# sch_light_rgb.net
KiCad netlist of a schematic drawn in EasyEDA
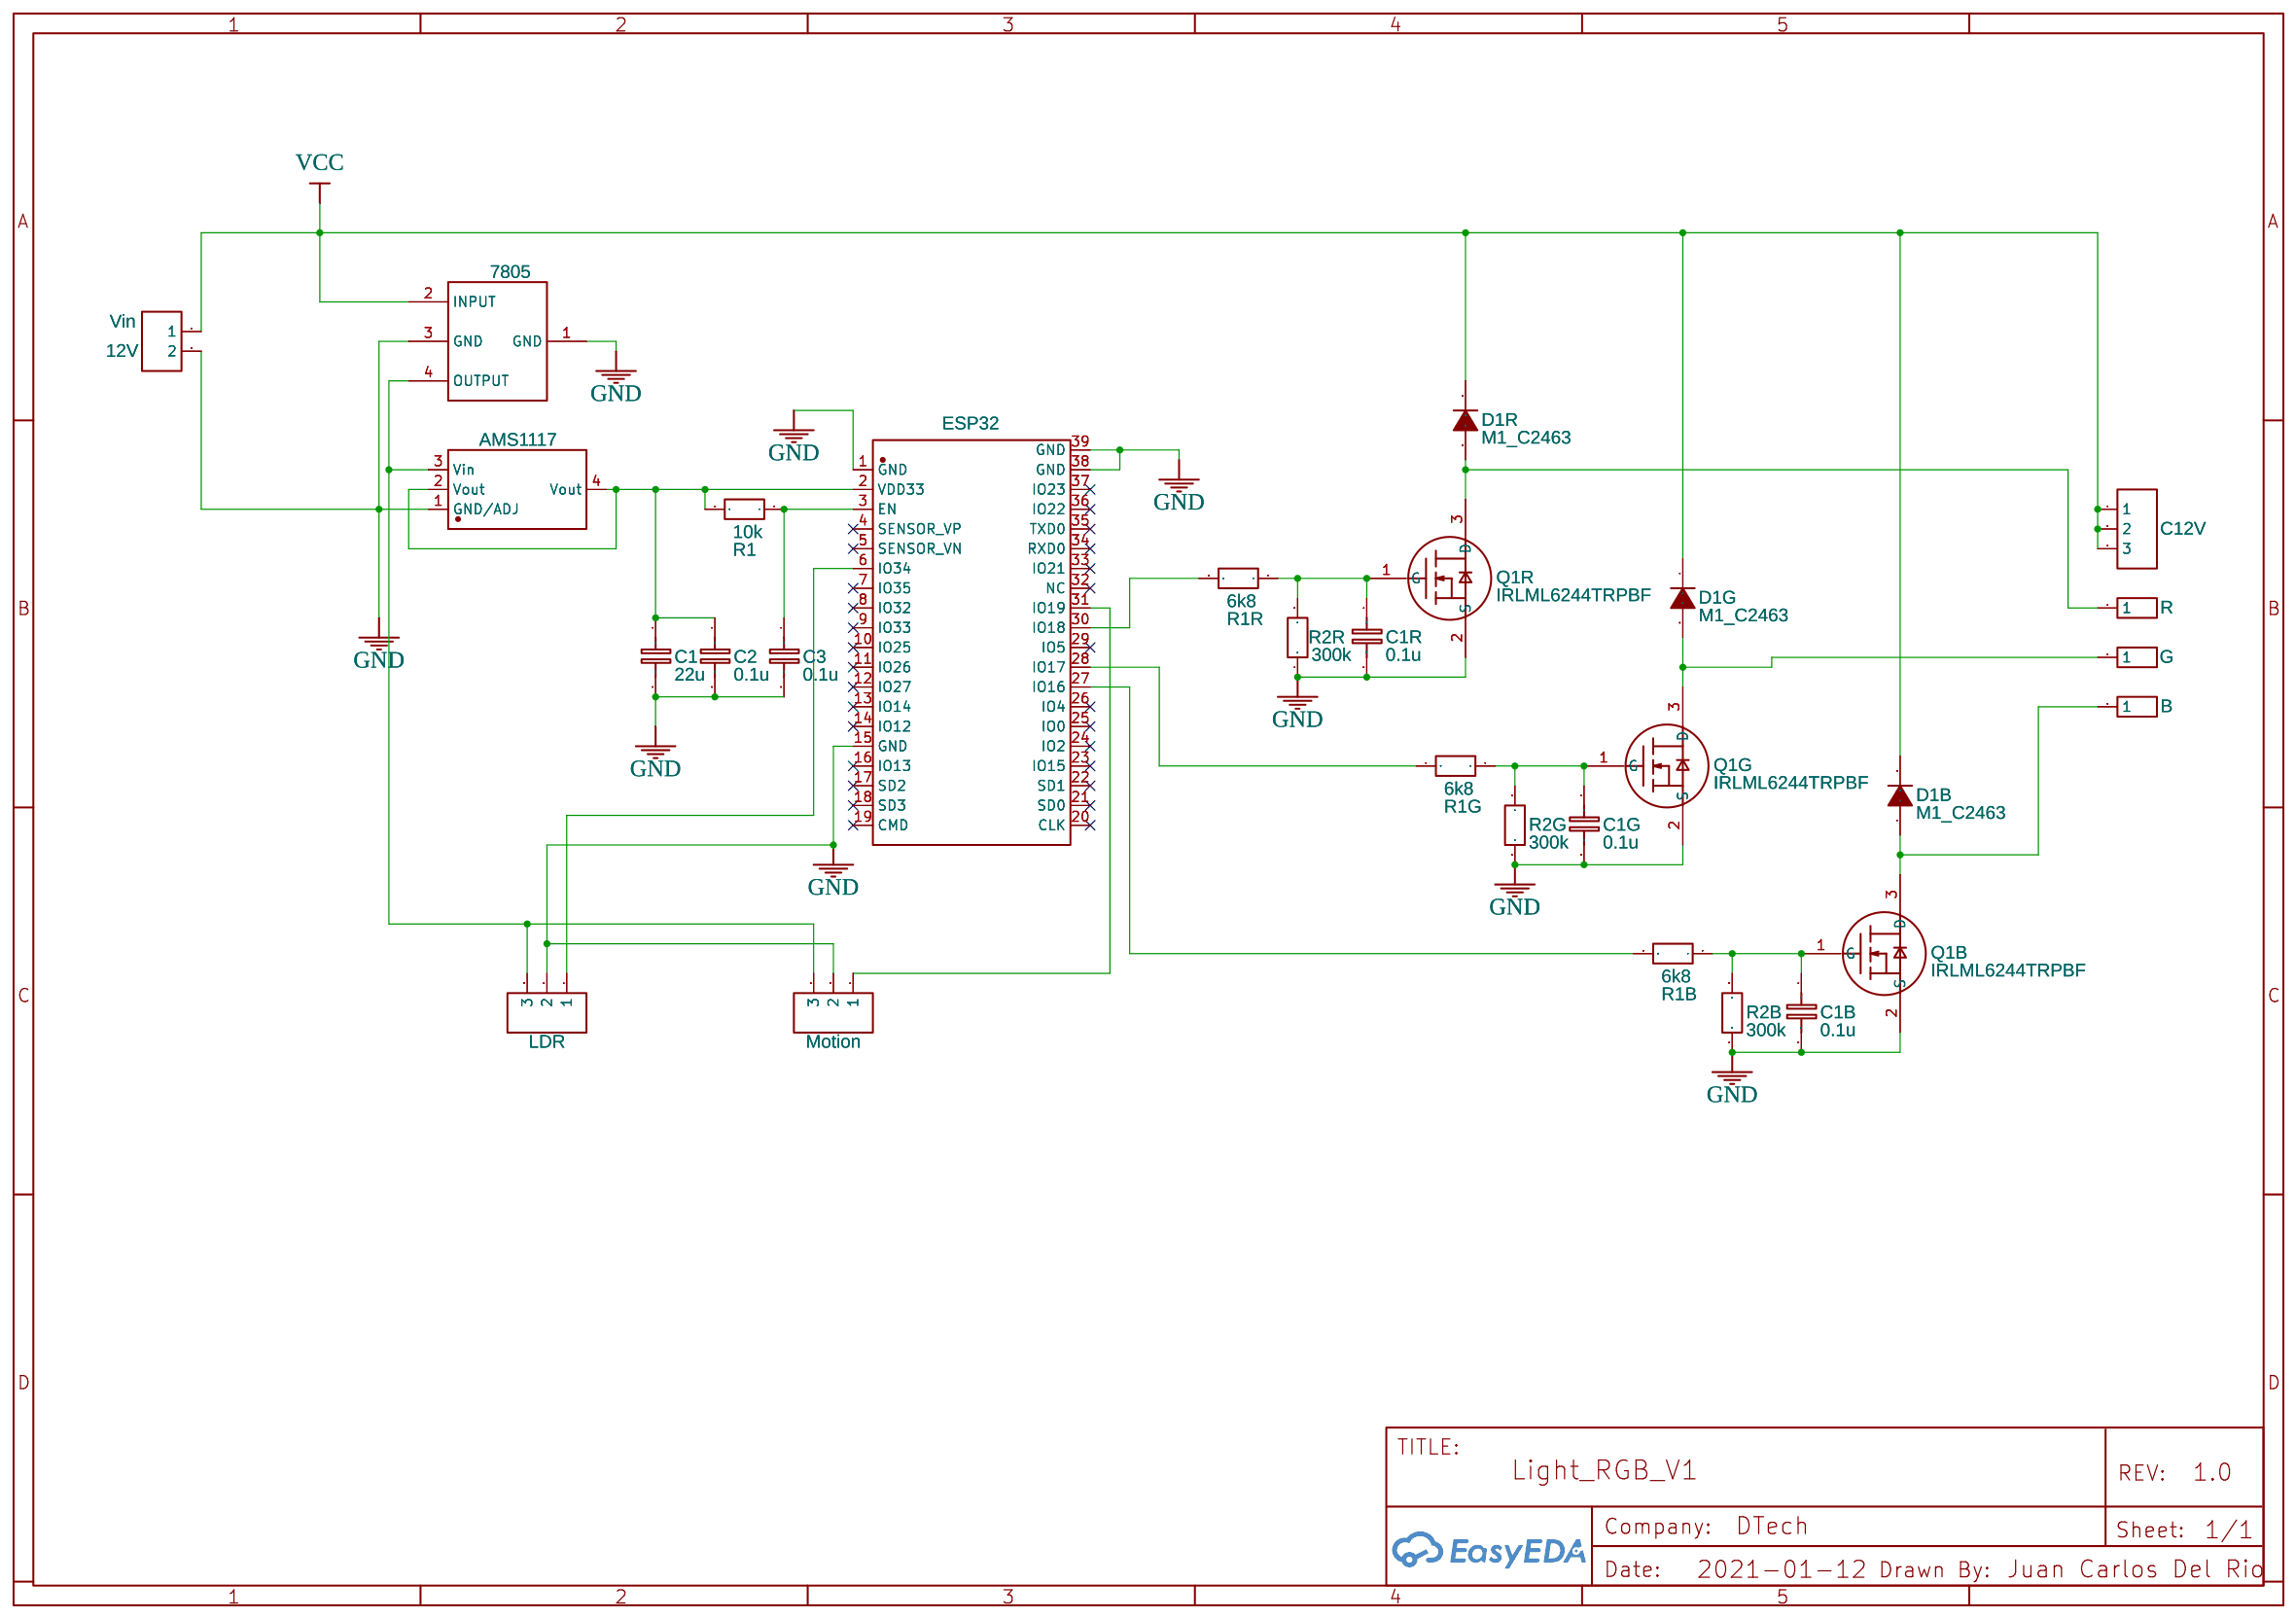
[diagram p0: schematic sheet]

(export (version "E")
  (design (tool "Eeschema 10.0.6"))
  (components
    (comp (ref "12V") (value "Vin") (libsource (lib "") (part "HDR-F-2.54_1x2")))
    (comp (ref "7805") (value "LM7805 SOT223-4") (libsource (lib "") (part "LM7805 SOT223-4")))
    (comp (ref "AMS1117")
      (value "AMS1117-3.3")
      (fields (field (name "Manufacturer") "AMS"))
      (libsource (lib "") (part "AMS1117-3.3"))
    )
    (comp (ref "B") (value "B") (libsource (lib "") (part "HDR-M-2.54_1x1_2")))
    (comp (ref "C1") (value "22u") (libsource (lib "") (part "C_0805_EU")))
    (comp (ref "C1B") (value "0.1u") (libsource (lib "") (part "C_0805_EU_1")))
    (comp (ref "C1G") (value "0.1u") (libsource (lib "") (part "C_0805_EU_2")))
    (comp (ref "C1R") (value "0.1u") (libsource (lib "") (part "C_0805_EU_3")))
    (comp (ref "C2") (value "0.1u") (libsource (lib "") (part "C_0805_EU")))
    (comp (ref "C3") (value "0.1u") (libsource (lib "") (part "C_0805_EU")))
    (comp (ref "C12V") (value "C12V") (libsource (lib "") (part "HDR-F-2.54_1x3")))
    (comp (ref "D1B")
      (value "M1_C2463")
      (fields (field (name "Manufacturer Part") "M1") (field (name "Manufacturer") "MDD"))
      (libsource (lib "") (part "M1_C2463_1"))
    )
    (comp (ref "D1G")
      (value "M1_C2463")
      (fields (field (name "Manufacturer Part") "M1") (field (name "Manufacturer") "MDD"))
      (libsource (lib "") (part "M1_C2463_2"))
    )
    (comp (ref "D1R")
      (value "M1_C2463")
      (fields (field (name "Manufacturer Part") "M1") (field (name "Manufacturer") "MDD"))
      (libsource (lib "") (part "M1_C2463"))
    )
    (comp (ref "ESP32")
      (value "ESP32-WROOM-32")
      (fields (field (name "Manufacturer") "Espressif Systems"))
      (libsource (lib "") (part "ESP32-WROOM-32"))
    )
    (comp (ref "G") (value "G") (libsource (lib "") (part "HDR-M-2.54_1x1")))
    (comp (ref "LDR") (value "LDR") (libsource (lib "") (part "HDR-F-2.54_1x3_1")))
    (comp (ref "MOTION") (value "Motion") (libsource (lib "") (part "HDR-F-2.54_1x3_2")))
    (comp (ref "Q1B")
      (value "IRLML6244TRPBF")
      (fields (field (name "Manufacturer") "Infineon"))
      (libsource (lib "") (part "IRLML6244TRPBF_2"))
    )
    (comp (ref "Q1G")
      (value "IRLML6244TRPBF")
      (fields (field (name "Manufacturer") "Infineon"))
      (libsource (lib "") (part "IRLML6244TRPBF"))
    )
    (comp (ref "Q1R")
      (value "IRLML6244TRPBF")
      (fields (field (name "Manufacturer") "Infineon"))
      (libsource (lib "") (part "IRLML6244TRPBF_1"))
    )
    (comp (ref "R") (value "R") (libsource (lib "") (part "HDR-M-2.54_1x1_1")))
    (comp (ref "R1") (value "10k") (libsource (lib "") (part "R_1206_EU_2")))
    (comp (ref "R1B") (value "6k8") (libsource (lib "") (part "R_1206_EU_1")))
    (comp (ref "R1G") (value "6k8") (libsource (lib "") (part "R_1206_EU_3")))
    (comp (ref "R1R") (value "6k8") (libsource (lib "") (part "R_1206_EU")))
    (comp (ref "R2B") (value "300k") (libsource (lib "") (part "R_1206_EU_5")))
    (comp (ref "R2G") (value "300k") (libsource (lib "") (part "R_1206_EU_6")))
    (comp (ref "R2R") (value "300k") (libsource (lib "") (part "R_1206_EU_4")))
  )
  (nets
    (net (code "1") (name "GND") (class "Default")
      (node (ref "12V") (pin "2") (pinfunction "2_2") (pintype "input"))
      (node (ref "7805") (pin "1") (pinfunction "GND_1") (pintype "unspecified"))
      (node (ref "7805") (pin "3") (pinfunction "GND_3") (pintype "unspecified"))
      (node (ref "AMS1117") (pin "1") (pinfunction "GND/ADJ_1") (pintype "unspecified"))
      (node (ref "C1") (pin "2") (pinfunction "2_2") (pintype "unspecified"))
      (node (ref "C1B") (pin "2") (pinfunction "2_2") (pintype "unspecified"))
      (node (ref "C1G") (pin "2") (pinfunction "2_2") (pintype "unspecified"))
      (node (ref "C1R") (pin "2") (pinfunction "2_2") (pintype "unspecified"))
      (node (ref "C2") (pin "2") (pinfunction "2_2") (pintype "unspecified"))
      (node (ref "C3") (pin "2") (pinfunction "2_2") (pintype "unspecified"))
      (node (ref "ESP32") (pin "1") (pinfunction "GND_1") (pintype "unspecified"))
      (node (ref "ESP32") (pin "15") (pinfunction "GND_15") (pintype "unspecified"))
      (node (ref "ESP32") (pin "38") (pinfunction "GND_38") (pintype "unspecified"))
      (node (ref "ESP32") (pin "39") (pinfunction "GND_39") (pintype "unspecified"))
      (node (ref "LDR") (pin "2") (pinfunction "2_2") (pintype "input"))
      (node (ref "MOTION") (pin "2") (pinfunction "2_2") (pintype "input"))
      (node (ref "Q1B") (pin "2") (pinfunction "S_2") (pintype "unspecified"))
      (node (ref "Q1G") (pin "2") (pinfunction "S_2") (pintype "unspecified"))
      (node (ref "Q1R") (pin "2") (pinfunction "S_2") (pintype "unspecified"))
      (node (ref "R2B") (pin "1") (pinfunction "1_1") (pintype "unspecified"))
      (node (ref "R2G") (pin "1") (pinfunction "1_1") (pintype "unspecified"))
      (node (ref "R2R") (pin "1") (pinfunction "1_1") (pintype "unspecified"))
    )
    (net (code "2") (name "Net-(7805-OUTPUT)") (class "Default")
      (node (ref "7805") (pin "4") (pinfunction "OUTPUT_4") (pintype "unspecified"))
      (node (ref "AMS1117") (pin "3") (pinfunction "Vin_3") (pintype "unspecified"))
      (node (ref "LDR") (pin "3") (pinfunction "3_3") (pintype "input"))
      (node (ref "MOTION") (pin "3") (pinfunction "3_3") (pintype "input"))
    )
    (net (code "3") (name "Net-(D1B-A)") (class "Default")
      (node (ref "B") (pin "1") (pinfunction "1_1") (pintype "input"))
      (node (ref "D1B") (pin "2") (pinfunction "A_2") (pintype "unspecified"))
      (node (ref "Q1B") (pin "3") (pinfunction "D_3") (pintype "unspecified"))
    )
    (net (code "4") (name "Net-(D1G-A)") (class "Default")
      (node (ref "D1G") (pin "2") (pinfunction "A_2") (pintype "unspecified"))
      (node (ref "G") (pin "1") (pinfunction "1_1") (pintype "input"))
      (node (ref "Q1G") (pin "3") (pinfunction "D_3") (pintype "unspecified"))
    )
    (net (code "5") (name "Net-(D1R-A)") (class "Default")
      (node (ref "D1R") (pin "2") (pinfunction "A_2") (pintype "unspecified"))
      (node (ref "Q1R") (pin "3") (pinfunction "D_3") (pintype "unspecified"))
      (node (ref "R") (pin "1") (pinfunction "1_1") (pintype "input"))
    )
    (net (code "6") (name "Net-(ESP32-EN)") (class "Default")
      (node (ref "C3") (pin "1") (pinfunction "1_1") (pintype "unspecified"))
      (node (ref "ESP32") (pin "3") (pinfunction "EN_3") (pintype "unspecified"))
      (node (ref "R1") (pin "1") (pinfunction "1_1") (pintype "unspecified"))
    )
    (net (code "7") (name "Net-(ESP32-IO16)") (class "Default")
      (node (ref "ESP32") (pin "27") (pinfunction "IO16_27") (pintype "unspecified"))
      (node (ref "R1B") (pin "2") (pinfunction "2_2") (pintype "unspecified"))
    )
    (net (code "8") (name "Net-(ESP32-IO17)") (class "Default")
      (node (ref "ESP32") (pin "28") (pinfunction "IO17_28") (pintype "unspecified"))
      (node (ref "R1G") (pin "2") (pinfunction "2_2") (pintype "unspecified"))
    )
    (net (code "9") (name "Net-(ESP32-IO18)") (class "Default")
      (node (ref "ESP32") (pin "30") (pinfunction "IO18_30") (pintype "unspecified"))
      (node (ref "R1R") (pin "2") (pinfunction "2_2") (pintype "unspecified"))
    )
    (net (code "10") (name "Net-(ESP32-IO19)") (class "Default")
      (node (ref "ESP32") (pin "31") (pinfunction "IO19_31") (pintype "unspecified"))
      (node (ref "MOTION") (pin "1") (pinfunction "1_1") (pintype "input"))
    )
    (net (code "11") (name "Net-(ESP32-IO34)") (class "Default")
      (node (ref "ESP32") (pin "6") (pinfunction "IO34_6") (pintype "unspecified"))
      (node (ref "LDR") (pin "1") (pinfunction "1_1") (pintype "input"))
    )
    (net (code "12") (name "Net-(ESP32-VDD33)") (class "Default")
      (node (ref "AMS1117") (pin "2") (pinfunction "Vout_2") (pintype "unspecified"))
      (node (ref "AMS1117") (pin "4") (pinfunction "Vout_4") (pintype "unspecified"))
      (node (ref "C1") (pin "1") (pinfunction "1_1") (pintype "unspecified"))
      (node (ref "C2") (pin "1") (pinfunction "1_1") (pintype "unspecified"))
      (node (ref "ESP32") (pin "2") (pinfunction "VDD33_2") (pintype "unspecified"))
      (node (ref "R1") (pin "2") (pinfunction "2_2") (pintype "unspecified"))
    )
    (net (code "13") (name "Net-(Q1B-G)") (class "Default")
      (node (ref "C1B") (pin "1") (pinfunction "1_1") (pintype "unspecified"))
      (node (ref "Q1B") (pin "1") (pinfunction "G_1") (pintype "unspecified"))
      (node (ref "R1B") (pin "1") (pinfunction "1_1") (pintype "unspecified"))
      (node (ref "R2B") (pin "2") (pinfunction "2_2") (pintype "unspecified"))
    )
    (net (code "14") (name "Net-(Q1G-G)") (class "Default")
      (node (ref "C1G") (pin "1") (pinfunction "1_1") (pintype "unspecified"))
      (node (ref "Q1G") (pin "1") (pinfunction "G_1") (pintype "unspecified"))
      (node (ref "R1G") (pin "1") (pinfunction "1_1") (pintype "unspecified"))
      (node (ref "R2G") (pin "2") (pinfunction "2_2") (pintype "unspecified"))
    )
    (net (code "15") (name "Net-(Q1R-G)") (class "Default")
      (node (ref "C1R") (pin "1") (pinfunction "1_1") (pintype "unspecified"))
      (node (ref "Q1R") (pin "1") (pinfunction "G_1") (pintype "unspecified"))
      (node (ref "R1R") (pin "1") (pinfunction "1_1") (pintype "unspecified"))
      (node (ref "R2R") (pin "2") (pinfunction "2_2") (pintype "unspecified"))
    )
    (net (code "16") (name "VCC") (class "Default")
      (node (ref "12V") (pin "1") (pinfunction "1_1") (pintype "input"))
      (node (ref "7805") (pin "2") (pinfunction "INPUT_2") (pintype "unspecified"))
      (node (ref "C12V") (pin "1") (pinfunction "1_1") (pintype "input"))
      (node (ref "C12V") (pin "2") (pinfunction "2_2") (pintype "input"))
      (node (ref "C12V") (pin "3") (pinfunction "3_3") (pintype "input"))
      (node (ref "D1B") (pin "1") (pinfunction "K_1") (pintype "unspecified"))
      (node (ref "D1G") (pin "1") (pinfunction "K_1") (pintype "unspecified"))
      (node (ref "D1R") (pin "1") (pinfunction "K_1") (pintype "unspecified"))
    )
    (net (code "17") (name "unconnected-(ESP32-CLK-Pad20)") (class "Default")
      (node (ref "ESP32") (pin "20") (pinfunction "CLK_20") (pintype "unspecified+no_connect"))
    )
    (net (code "18") (name "unconnected-(ESP32-CMD-Pad19)") (class "Default")
      (node (ref "ESP32") (pin "19") (pinfunction "CMD_19") (pintype "unspecified+no_connect"))
    )
    (net (code "19") (name "unconnected-(ESP32-IO0-Pad25)") (class "Default")
      (node (ref "ESP32") (pin "25") (pinfunction "IO0_25") (pintype "unspecified+no_connect"))
    )
    (net (code "20") (name "unconnected-(ESP32-IO2-Pad24)") (class "Default")
      (node (ref "ESP32") (pin "24") (pinfunction "IO2_24") (pintype "unspecified+no_connect"))
    )
    (net (code "21") (name "unconnected-(ESP32-IO4-Pad26)") (class "Default")
      (node (ref "ESP32") (pin "26") (pinfunction "IO4_26") (pintype "unspecified+no_connect"))
    )
    (net (code "22") (name "unconnected-(ESP32-IO5-Pad29)") (class "Default")
      (node (ref "ESP32") (pin "29") (pinfunction "IO5_29") (pintype "unspecified+no_connect"))
    )
    (net (code "23") (name "unconnected-(ESP32-IO12-Pad14)") (class "Default")
      (node (ref "ESP32") (pin "14") (pinfunction "IO12_14") (pintype "unspecified+no_connect"))
    )
    (net (code "24") (name "unconnected-(ESP32-IO13-Pad16)") (class "Default")
      (node (ref "ESP32") (pin "16") (pinfunction "IO13_16") (pintype "unspecified+no_connect"))
    )
    (net (code "25") (name "unconnected-(ESP32-IO14-Pad13)") (class "Default")
      (node (ref "ESP32") (pin "13") (pinfunction "IO14_13") (pintype "unspecified+no_connect"))
    )
    (net (code "26") (name "unconnected-(ESP32-IO15-Pad23)") (class "Default")
      (node (ref "ESP32") (pin "23") (pinfunction "IO15_23") (pintype "unspecified+no_connect"))
    )
    (net (code "27") (name "unconnected-(ESP32-IO21-Pad33)") (class "Default")
      (node (ref "ESP32") (pin "33") (pinfunction "IO21_33") (pintype "unspecified+no_connect"))
    )
    (net (code "28") (name "unconnected-(ESP32-IO22-Pad36)") (class "Default")
      (node (ref "ESP32") (pin "36") (pinfunction "IO22_36") (pintype "unspecified+no_connect"))
    )
    (net (code "29") (name "unconnected-(ESP32-IO23-Pad37)") (class "Default")
      (node (ref "ESP32") (pin "37") (pinfunction "IO23_37") (pintype "unspecified+no_connect"))
    )
    (net (code "30") (name "unconnected-(ESP32-IO25-Pad10)") (class "Default")
      (node (ref "ESP32") (pin "10") (pinfunction "IO25_10") (pintype "unspecified+no_connect"))
    )
    (net (code "31") (name "unconnected-(ESP32-IO26-Pad11)") (class "Default")
      (node (ref "ESP32") (pin "11") (pinfunction "IO26_11") (pintype "unspecified+no_connect"))
    )
    (net (code "32") (name "unconnected-(ESP32-IO27-Pad12)") (class "Default")
      (node (ref "ESP32") (pin "12") (pinfunction "IO27_12") (pintype "unspecified+no_connect"))
    )
    (net (code "33") (name "unconnected-(ESP32-IO32-Pad8)") (class "Default")
      (node (ref "ESP32") (pin "8") (pinfunction "IO32_8") (pintype "unspecified+no_connect"))
    )
    (net (code "34") (name "unconnected-(ESP32-IO33-Pad9)") (class "Default")
      (node (ref "ESP32") (pin "9") (pinfunction "IO33_9") (pintype "unspecified+no_connect"))
    )
    (net (code "35") (name "unconnected-(ESP32-IO35-Pad7)") (class "Default")
      (node (ref "ESP32") (pin "7") (pinfunction "IO35_7") (pintype "unspecified+no_connect"))
    )
    (net (code "36") (name "unconnected-(ESP32-NC-Pad32)") (class "Default")
      (node (ref "ESP32") (pin "32") (pinfunction "NC_32") (pintype "unspecified+no_connect"))
    )
    (net (code "37") (name "unconnected-(ESP32-RXD0-Pad34)") (class "Default")
      (node (ref "ESP32") (pin "34") (pinfunction "RXD0_34") (pintype "unspecified+no_connect"))
    )
    (net (code "38") (name "unconnected-(ESP32-SD0-Pad21)") (class "Default")
      (node (ref "ESP32") (pin "21") (pinfunction "SD0_21") (pintype "unspecified+no_connect"))
    )
    (net (code "39") (name "unconnected-(ESP32-SD1-Pad22)") (class "Default")
      (node (ref "ESP32") (pin "22") (pinfunction "SD1_22") (pintype "unspecified+no_connect"))
    )
    (net (code "40") (name "unconnected-(ESP32-SD2-Pad17)") (class "Default")
      (node (ref "ESP32") (pin "17") (pinfunction "SD2_17") (pintype "unspecified+no_connect"))
    )
    (net (code "41") (name "unconnected-(ESP32-SD3-Pad18)") (class "Default")
      (node (ref "ESP32") (pin "18") (pinfunction "SD3_18") (pintype "unspecified+no_connect"))
    )
    (net (code "42") (name "unconnected-(ESP32-SENSOR_VN-Pad5)") (class "Default")
      (node (ref "ESP32") (pin "5") (pinfunction "SENSOR_VN_5") (pintype "unspecified+no_connect"))
    )
    (net (code "43") (name "unconnected-(ESP32-SENSOR_VP-Pad4)") (class "Default")
      (node (ref "ESP32") (pin "4") (pinfunction "SENSOR_VP_4") (pintype "unspecified+no_connect"))
    )
    (net (code "44") (name "unconnected-(ESP32-TXD0-Pad35)") (class "Default")
      (node (ref "ESP32") (pin "35") (pinfunction "TXD0_35") (pintype "unspecified+no_connect"))
    )
  )
)
